# design.net
KiCad netlist of a schematic drawn in Altium Designer
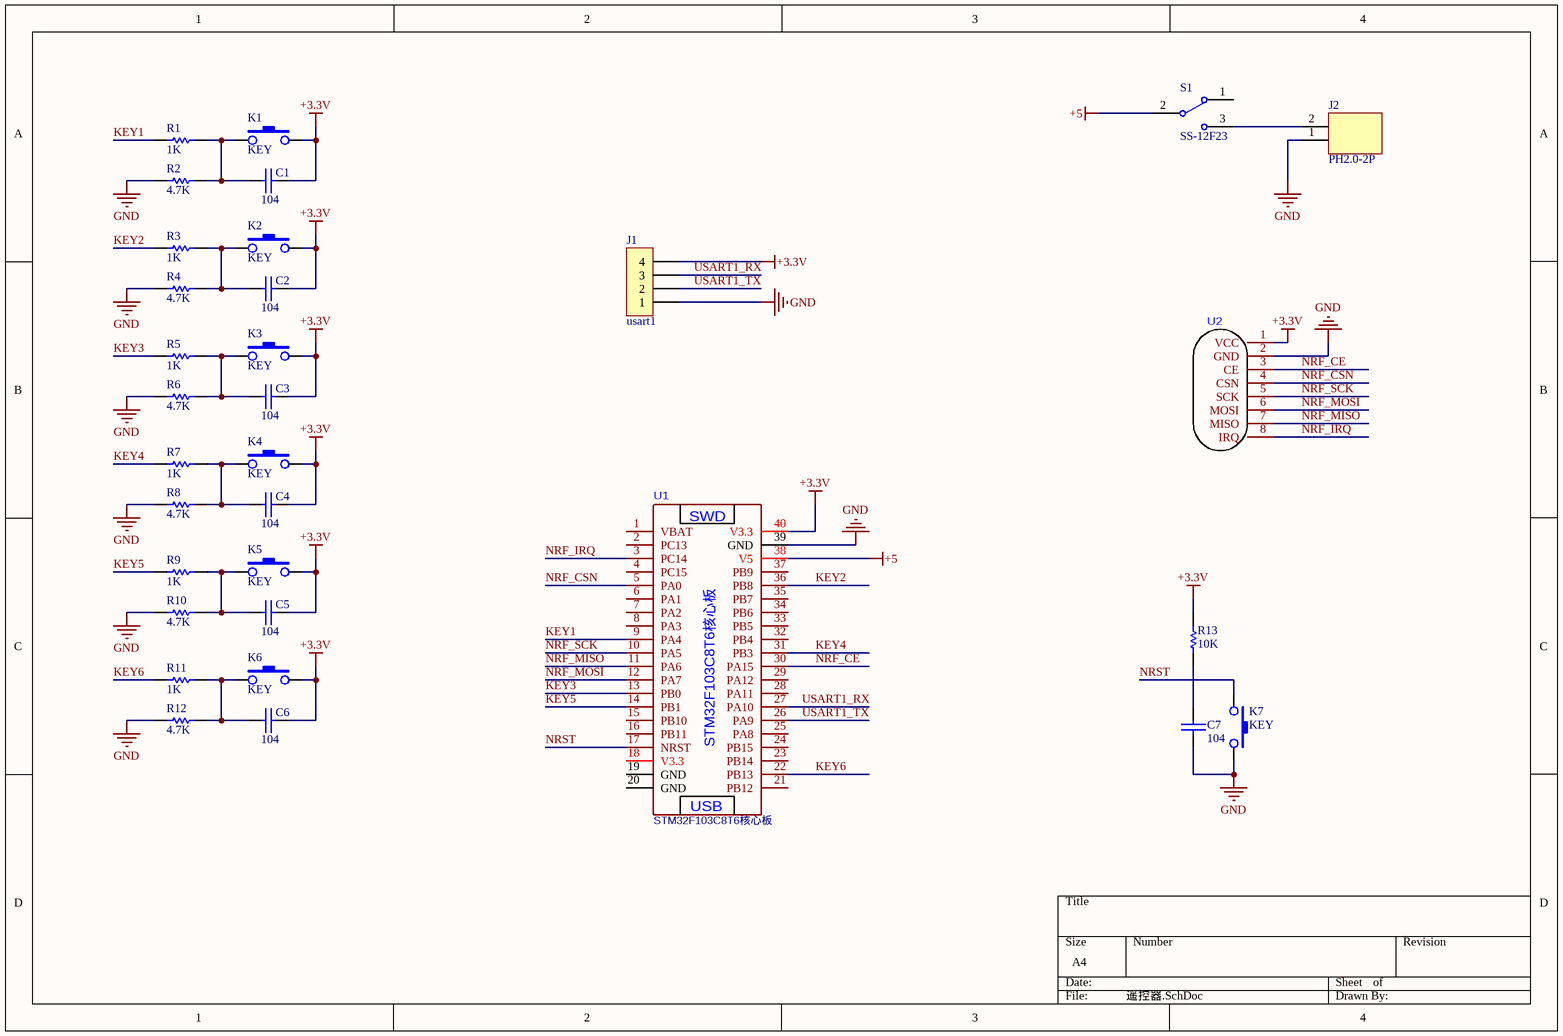
[diagram p0: 遥控器.SchDoc]

(export (version "E")
  (design (tool "Eeschema 10.0.6"))
  (components
    (comp (ref "C1")
      (value "104")
      (footprint "0805C")
      (description "无极性电容")
      (libsource (lib "电容") (part "CAP"))
    )
    (comp (ref "C2")
      (value "104")
      (footprint "0805C")
      (description "无极性电容")
      (libsource (lib "电容") (part "CAP"))
    )
    (comp (ref "C3")
      (value "104")
      (footprint "0805C")
      (description "无极性电容")
      (libsource (lib "电容") (part "CAP"))
    )
    (comp (ref "C4")
      (value "104")
      (footprint "0805C")
      (description "无极性电容")
      (libsource (lib "电容") (part "CAP"))
    )
    (comp (ref "C5")
      (value "104")
      (footprint "0805C")
      (description "无极性电容")
      (libsource (lib "电容") (part "CAP"))
    )
    (comp (ref "C6")
      (value "104")
      (footprint "0805C")
      (description "无极性电容")
      (libsource (lib "电容") (part "CAP"))
    )
    (comp (ref "C7")
      (value "104")
      (footprint "0805C")
      (description "无极性电容")
      (libsource (lib "电容") (part "CAP"))
    )
    (comp (ref "J1")
      (value "usart1")
      (footprint "Pin HDR1X4/2.54mm-S")
      (libsource (lib "排针") (part "Pin HDR1X4"))
    )
    (comp (ref "J2") (value "PH2.0-2P") (footprint "PH2.0S-2P") (libsource (lib "PH") (part "PH2.0-2P")))
    (comp (ref "K1") (value "KEY") (footprint "DIP-6X6X5") (libsource (lib "轻触开关") (part "KEY")))
    (comp (ref "K2") (value "KEY") (footprint "DIP-6X6X5") (libsource (lib "轻触开关") (part "KEY")))
    (comp (ref "K3") (value "KEY") (footprint "DIP-6X6X5") (libsource (lib "轻触开关") (part "KEY")))
    (comp (ref "K4") (value "KEY") (footprint "DIP-6X6X5") (libsource (lib "轻触开关") (part "KEY")))
    (comp (ref "K5") (value "KEY") (footprint "DIP-6X6X5") (libsource (lib "轻触开关") (part "KEY")))
    (comp (ref "K6") (value "KEY") (footprint "DIP-6X6X5") (libsource (lib "轻触开关") (part "KEY")))
    (comp (ref "K7") (value "KEY") (footprint "DIP-6X6X5") (libsource (lib "轻触开关") (part "KEY")))
    (comp (ref "R1") (value "1K") (footprint "0805R") (libsource (lib "电阻") (part "RES")))
    (comp (ref "R2") (value "4.7K") (footprint "0805R") (libsource (lib "电阻") (part "RES")))
    (comp (ref "R3") (value "1K") (footprint "0805R") (libsource (lib "电阻") (part "RES")))
    (comp (ref "R4") (value "4.7K") (footprint "0805R") (libsource (lib "电阻") (part "RES")))
    (comp (ref "R5") (value "1K") (footprint "0805R") (libsource (lib "电阻") (part "RES")))
    (comp (ref "R6") (value "4.7K") (footprint "0805R") (libsource (lib "电阻") (part "RES")))
    (comp (ref "R7") (value "1K") (footprint "0805R") (libsource (lib "电阻") (part "RES")))
    (comp (ref "R8") (value "4.7K") (footprint "0805R") (libsource (lib "电阻") (part "RES")))
    (comp (ref "R9") (value "1K") (footprint "0805R") (libsource (lib "电阻") (part "RES")))
    (comp (ref "R10") (value "4.7K") (footprint "0805R") (libsource (lib "电阻") (part "RES")))
    (comp (ref "R11") (value "1K") (footprint "0805R") (libsource (lib "电阻") (part "RES")))
    (comp (ref "R12") (value "4.7K") (footprint "0805R") (libsource (lib "电阻") (part "RES")))
    (comp (ref "R13") (value "10K") (footprint "0805R") (libsource (lib "电阻") (part "RES")))
    (comp (ref "S1") (value "SS-12F23") (footprint "SS-12F23") (libsource (lib "电源开关") (part "SS-12F23")))
    (comp (ref "U1")
      (value "STM32F103C8T6核心板")
      (footprint "STM32F103")
      (libsource (lib "zy lib") (part "STM32F103C8T6核心板"))
    )
    (comp (ref "U2")
      (value "~")
      (footprint "NRF24L01+ SMD")
      (libsource (lib "altium-import") (part "root_0_nRF24l01_"))
    )
  )
  (nets
    (net (code "1") (name "+3.3V") (class "Default")
      (node (ref "C1") (pin "2") (pinfunction "2_2") (pintype "passive"))
      (node (ref "C2") (pin "2") (pinfunction "2_2") (pintype "passive"))
      (node (ref "C3") (pin "2") (pinfunction "2_2") (pintype "passive"))
      (node (ref "C4") (pin "2") (pinfunction "2_2") (pintype "passive"))
      (node (ref "C5") (pin "2") (pinfunction "2_2") (pintype "passive"))
      (node (ref "C6") (pin "2") (pinfunction "2_2") (pintype "passive"))
      (node (ref "J1") (pin "4") (pinfunction "4_4") (pintype "passive"))
      (node (ref "K1") (pin "3") (pinfunction "3_3") (pintype "passive"))
      (node (ref "K2") (pin "3") (pinfunction "3_3") (pintype "passive"))
      (node (ref "K3") (pin "3") (pinfunction "3_3") (pintype "passive"))
      (node (ref "K4") (pin "3") (pinfunction "3_3") (pintype "passive"))
      (node (ref "K5") (pin "3") (pinfunction "3_3") (pintype "passive"))
      (node (ref "K6") (pin "3") (pinfunction "3_3") (pintype "passive"))
      (node (ref "R13") (pin "2") (pinfunction "2_2") (pintype "passive"))
      (node (ref "U1") (pin "40") (pinfunction "V3.3_40") (pintype "passive"))
      (node (ref "U2") (pin "1") (pinfunction "VCC_1") (pintype "passive"))
    )
    (net (code "2") (name "+5") (class "Default")
      (node (ref "S1") (pin "2") (pinfunction "2_2") (pintype "passive"))
      (node (ref "U1") (pin "38") (pinfunction "V5_38") (pintype "passive"))
    )
    (net (code "3") (name "/KEY1") (class "Default")
      (node (ref "R1") (pin "1") (pinfunction "1_1") (pintype "passive"))
      (node (ref "U1") (pin "9") (pinfunction "PA4_9") (pintype "passive"))
    )
    (net (code "4") (name "/KEY2") (class "Default")
      (node (ref "R3") (pin "1") (pinfunction "1_1") (pintype "passive"))
      (node (ref "U1") (pin "36") (pinfunction "PB8_36") (pintype "passive"))
    )
    (net (code "5") (name "/KEY3") (class "Default")
      (node (ref "R5") (pin "1") (pinfunction "1_1") (pintype "passive"))
      (node (ref "U1") (pin "13") (pinfunction "PB0_13") (pintype "passive"))
    )
    (net (code "6") (name "/KEY4") (class "Default")
      (node (ref "R7") (pin "1") (pinfunction "1_1") (pintype "passive"))
      (node (ref "U1") (pin "31") (pinfunction "PB3_31") (pintype "passive"))
    )
    (net (code "7") (name "/KEY5") (class "Default")
      (node (ref "R9") (pin "1") (pinfunction "1_1") (pintype "passive"))
      (node (ref "U1") (pin "14") (pinfunction "PB1_14") (pintype "passive"))
    )
    (net (code "8") (name "/KEY6") (class "Default")
      (node (ref "R11") (pin "1") (pinfunction "1_1") (pintype "passive"))
      (node (ref "U1") (pin "22") (pinfunction "PB13_22") (pintype "passive"))
    )
    (net (code "9") (name "/NRF_CE") (class "Default")
      (node (ref "U1") (pin "30") (pinfunction "PA15_30") (pintype "passive"))
      (node (ref "U2") (pin "3") (pinfunction "CE_3") (pintype "passive"))
    )
    (net (code "10") (name "/NRF_CSN") (class "Default")
      (node (ref "U1") (pin "5") (pinfunction "PA0_5") (pintype "passive"))
      (node (ref "U2") (pin "4") (pinfunction "CSN_4") (pintype "passive"))
    )
    (net (code "11") (name "/NRF_IRQ") (class "Default")
      (node (ref "U1") (pin "3") (pinfunction "PC14_3") (pintype "passive"))
      (node (ref "U2") (pin "8") (pinfunction "IRQ_8") (pintype "passive"))
    )
    (net (code "12") (name "/NRF_MISO") (class "Default")
      (node (ref "U1") (pin "11") (pinfunction "PA6_11") (pintype "passive"))
      (node (ref "U2") (pin "7") (pinfunction "MISO_7") (pintype "passive"))
    )
    (net (code "13") (name "/NRF_MOSI") (class "Default")
      (node (ref "U1") (pin "12") (pinfunction "PA7_12") (pintype "passive"))
      (node (ref "U2") (pin "6") (pinfunction "MOSI_6") (pintype "passive"))
    )
    (net (code "14") (name "/NRF_SCK") (class "Default")
      (node (ref "U1") (pin "10") (pinfunction "PA5_10") (pintype "passive"))
      (node (ref "U2") (pin "5") (pinfunction "SCK_5") (pintype "passive"))
    )
    (net (code "15") (name "/NRST") (class "Default")
      (node (ref "K7") (pin "1") (pinfunction "1_1") (pintype "passive"))
      (node (ref "U1") (pin "17") (pinfunction "NRST_17") (pintype "passive"))
    )
    (net (code "16") (name "/USART1_RX") (class "Default")
      (node (ref "J1") (pin "3") (pinfunction "3_3") (pintype "passive"))
      (node (ref "U1") (pin "27") (pinfunction "PA10_27") (pintype "passive"))
    )
    (net (code "17") (name "/USART1_TX") (class "Default")
      (node (ref "J1") (pin "2") (pinfunction "2_2") (pintype "passive"))
      (node (ref "U1") (pin "26") (pinfunction "PA9_26") (pintype "passive"))
    )
    (net (code "18") (name "GND") (class "Default")
      (node (ref "C7") (pin "1") (pinfunction "1_1") (pintype "passive"))
      (node (ref "J1") (pin "1") (pinfunction "1_1") (pintype "passive"))
      (node (ref "J2") (pin "1") (pinfunction "1_1") (pintype "passive"))
      (node (ref "K7") (pin "3") (pinfunction "3_3") (pintype "passive"))
      (node (ref "R10") (pin "1") (pinfunction "1_1") (pintype "passive"))
      (node (ref "R12") (pin "1") (pinfunction "1_1") (pintype "passive"))
      (node (ref "R2") (pin "1") (pinfunction "1_1") (pintype "passive"))
      (node (ref "R4") (pin "1") (pinfunction "1_1") (pintype "passive"))
      (node (ref "R6") (pin "1") (pinfunction "1_1") (pintype "passive"))
      (node (ref "R8") (pin "1") (pinfunction "1_1") (pintype "passive"))
      (node (ref "U1") (pin "39") (pinfunction "GND_39") (pintype "passive"))
      (node (ref "U2") (pin "2") (pinfunction "GND_2") (pintype "passive"))
    )
    (net (code "19") (name "Net-(C1-Pad1)") (class "Default")
      (node (ref "C1") (pin "1") (pinfunction "1_1") (pintype "passive"))
      (node (ref "K1") (pin "1") (pinfunction "1_1") (pintype "passive"))
      (node (ref "R1") (pin "2") (pinfunction "2_2") (pintype "passive"))
      (node (ref "R2") (pin "2") (pinfunction "2_2") (pintype "passive"))
    )
    (net (code "20") (name "Net-(C2-Pad1)") (class "Default")
      (node (ref "C2") (pin "1") (pinfunction "1_1") (pintype "passive"))
      (node (ref "K2") (pin "1") (pinfunction "1_1") (pintype "passive"))
      (node (ref "R3") (pin "2") (pinfunction "2_2") (pintype "passive"))
      (node (ref "R4") (pin "2") (pinfunction "2_2") (pintype "passive"))
    )
    (net (code "21") (name "Net-(C3-Pad1)") (class "Default")
      (node (ref "C3") (pin "1") (pinfunction "1_1") (pintype "passive"))
      (node (ref "K3") (pin "1") (pinfunction "1_1") (pintype "passive"))
      (node (ref "R5") (pin "2") (pinfunction "2_2") (pintype "passive"))
      (node (ref "R6") (pin "2") (pinfunction "2_2") (pintype "passive"))
    )
    (net (code "22") (name "Net-(C4-Pad1)") (class "Default")
      (node (ref "C4") (pin "1") (pinfunction "1_1") (pintype "passive"))
      (node (ref "K4") (pin "1") (pinfunction "1_1") (pintype "passive"))
      (node (ref "R7") (pin "2") (pinfunction "2_2") (pintype "passive"))
      (node (ref "R8") (pin "2") (pinfunction "2_2") (pintype "passive"))
    )
    (net (code "23") (name "Net-(C5-Pad1)") (class "Default")
      (node (ref "C5") (pin "1") (pinfunction "1_1") (pintype "passive"))
      (node (ref "K5") (pin "1") (pinfunction "1_1") (pintype "passive"))
      (node (ref "R10") (pin "2") (pinfunction "2_2") (pintype "passive"))
      (node (ref "R9") (pin "2") (pinfunction "2_2") (pintype "passive"))
    )
    (net (code "24") (name "Net-(C6-Pad1)") (class "Default")
      (node (ref "C6") (pin "1") (pinfunction "1_1") (pintype "passive"))
      (node (ref "K6") (pin "1") (pinfunction "1_1") (pintype "passive"))
      (node (ref "R11") (pin "2") (pinfunction "2_2") (pintype "passive"))
      (node (ref "R12") (pin "2") (pinfunction "2_2") (pintype "passive"))
    )
    (net (code "25") (name "Net-(C7-Pad2)") (class "Default")
      (node (ref "C7") (pin "2") (pinfunction "2_2") (pintype "passive"))
      (node (ref "R13") (pin "1") (pinfunction "1_1") (pintype "passive"))
    )
    (net (code "26") (name "Net-(J2-Pad2)") (class "Default")
      (node (ref "J2") (pin "2") (pinfunction "2_2") (pintype "passive"))
      (node (ref "S1") (pin "3") (pinfunction "3_3") (pintype "passive"))
    )
    (net (code "27") (name "unconnected-(S1-Pad1)") (class "Default")
      (node (ref "S1") (pin "1") (pinfunction "1_1") (pintype "passive"))
    )
    (net (code "28") (name "unconnected-(U1-GND-Pad19)") (class "Default")
      (node (ref "U1") (pin "19") (pinfunction "GND_19") (pintype "passive"))
    )
    (net (code "29") (name "unconnected-(U1-GND-Pad20)") (class "Default")
      (node (ref "U1") (pin "20") (pinfunction "GND_20") (pintype "passive"))
    )
    (net (code "30") (name "unconnected-(U1-PA1-Pad6)") (class "Default")
      (node (ref "U1") (pin "6") (pinfunction "PA1_6") (pintype "passive"))
    )
    (net (code "31") (name "unconnected-(U1-PA2-Pad7)") (class "Default")
      (node (ref "U1") (pin "7") (pinfunction "PA2_7") (pintype "passive"))
    )
    (net (code "32") (name "unconnected-(U1-PA3-Pad8)") (class "Default")
      (node (ref "U1") (pin "8") (pinfunction "PA3_8") (pintype "passive"))
    )
    (net (code "33") (name "unconnected-(U1-PA8-Pad25)") (class "Default")
      (node (ref "U1") (pin "25") (pinfunction "PA8_25") (pintype "passive"))
    )
    (net (code "34") (name "unconnected-(U1-PA11-Pad28)") (class "Default")
      (node (ref "U1") (pin "28") (pinfunction "PA11_28") (pintype "passive"))
    )
    (net (code "35") (name "unconnected-(U1-PA12-Pad29)") (class "Default")
      (node (ref "U1") (pin "29") (pinfunction "PA12_29") (pintype "passive"))
    )
    (net (code "36") (name "unconnected-(U1-PB4-Pad32)") (class "Default")
      (node (ref "U1") (pin "32") (pinfunction "PB4_32") (pintype "passive"))
    )
    (net (code "37") (name "unconnected-(U1-PB5-Pad33)") (class "Default")
      (node (ref "U1") (pin "33") (pinfunction "PB5_33") (pintype "passive"))
    )
    (net (code "38") (name "unconnected-(U1-PB6-Pad34)") (class "Default")
      (node (ref "U1") (pin "34") (pinfunction "PB6_34") (pintype "passive"))
    )
    (net (code "39") (name "unconnected-(U1-PB7-Pad35)") (class "Default")
      (node (ref "U1") (pin "35") (pinfunction "PB7_35") (pintype "passive"))
    )
    (net (code "40") (name "unconnected-(U1-PB9-Pad37)") (class "Default")
      (node (ref "U1") (pin "37") (pinfunction "PB9_37") (pintype "passive"))
    )
    (net (code "41") (name "unconnected-(U1-PB10-Pad15)") (class "Default")
      (node (ref "U1") (pin "15") (pinfunction "PB10_15") (pintype "passive"))
    )
    (net (code "42") (name "unconnected-(U1-PB11-Pad16)") (class "Default")
      (node (ref "U1") (pin "16") (pinfunction "PB11_16") (pintype "passive"))
    )
    (net (code "43") (name "unconnected-(U1-PB12-Pad21)") (class "Default")
      (node (ref "U1") (pin "21") (pinfunction "PB12_21") (pintype "passive"))
    )
    (net (code "44") (name "unconnected-(U1-PB14-Pad23)") (class "Default")
      (node (ref "U1") (pin "23") (pinfunction "PB14_23") (pintype "passive"))
    )
    (net (code "45") (name "unconnected-(U1-PB15-Pad24)") (class "Default")
      (node (ref "U1") (pin "24") (pinfunction "PB15_24") (pintype "passive"))
    )
    (net (code "46") (name "unconnected-(U1-PC13-Pad2)") (class "Default")
      (node (ref "U1") (pin "2") (pinfunction "PC13_2") (pintype "passive"))
    )
    (net (code "47") (name "unconnected-(U1-PC15-Pad4)") (class "Default")
      (node (ref "U1") (pin "4") (pinfunction "PC15_4") (pintype "passive"))
    )
    (net (code "48") (name "unconnected-(U1-V3.3-Pad18)") (class "Default")
      (node (ref "U1") (pin "18") (pinfunction "V3.3_18") (pintype "passive"))
    )
    (net (code "49") (name "unconnected-(U1-VBAT-Pad1)") (class "Default")
      (node (ref "U1") (pin "1") (pinfunction "VBAT_1") (pintype "passive"))
    )
  )
)
